# DisplayBoad.net
KiCad netlist of a schematic drawn in EAGLE
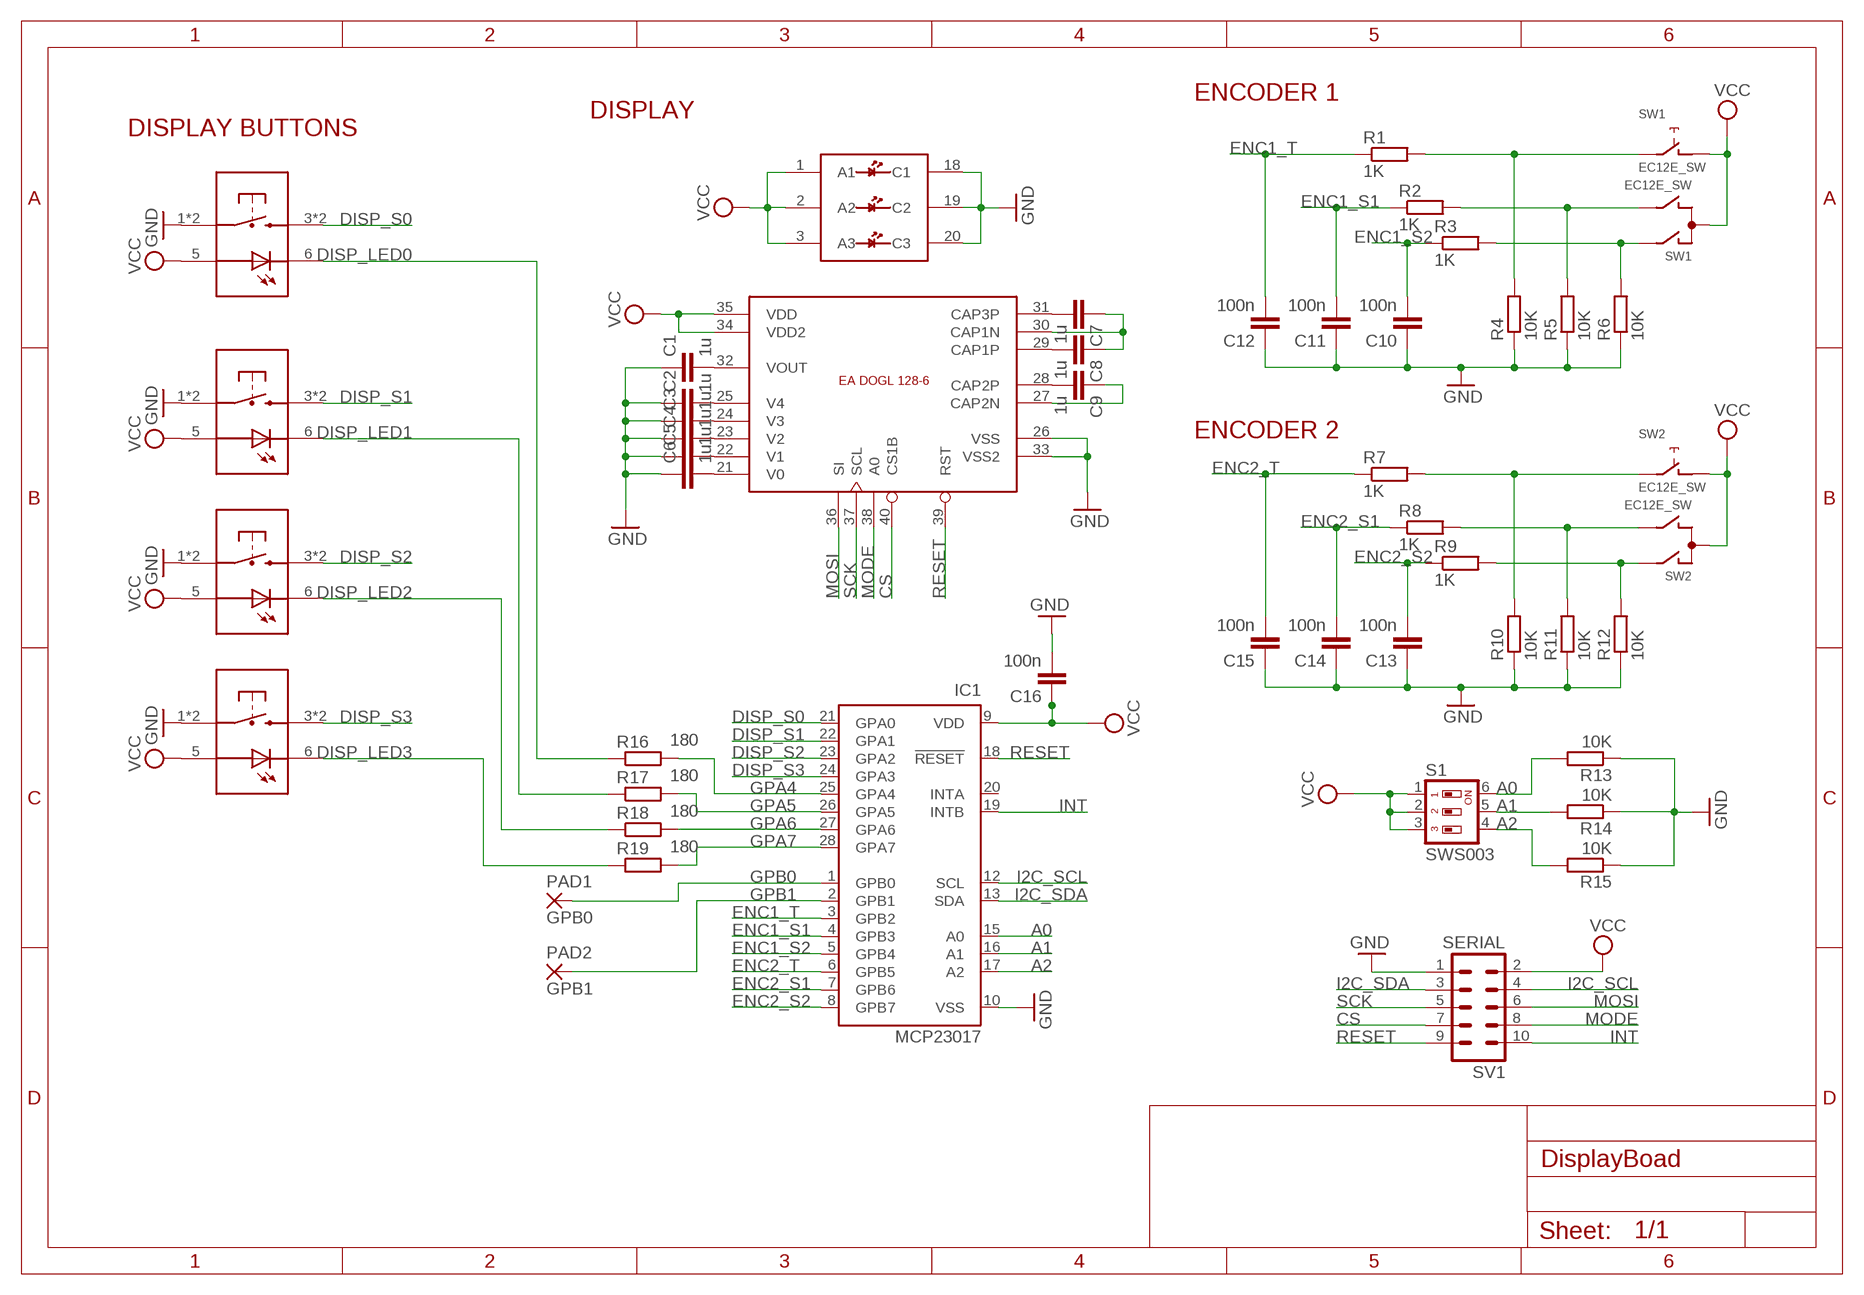
[diagram p0: schematic, sheet 1]

(export (version "E")
  (design (tool "Eeschema 10.0.6"))
  (components
    (comp (ref "C1")
      (value "1u")
      (footprint "eagle-import:C0805")
      (libsource (lib "eagle-import") (part "C-EUC0805"))
    )
    (comp (ref "C2")
      (value "1u")
      (footprint "eagle-import:C0805")
      (libsource (lib "eagle-import") (part "C-EUC0805"))
    )
    (comp (ref "C3")
      (value "1u")
      (footprint "eagle-import:C0805")
      (libsource (lib "eagle-import") (part "C-EUC0805"))
    )
    (comp (ref "C4")
      (value "1u")
      (footprint "eagle-import:C0805")
      (libsource (lib "eagle-import") (part "C-EUC0805"))
    )
    (comp (ref "C5")
      (value "1u")
      (footprint "eagle-import:C0805")
      (libsource (lib "eagle-import") (part "C-EUC0805"))
    )
    (comp (ref "C6")
      (value "1u")
      (footprint "eagle-import:C0805")
      (libsource (lib "eagle-import") (part "C-EUC0805"))
    )
    (comp (ref "C7")
      (value "1u")
      (footprint "eagle-import:C0805")
      (libsource (lib "eagle-import") (part "C-EUC0805"))
    )
    (comp (ref "C8")
      (value "1u")
      (footprint "eagle-import:C0805")
      (libsource (lib "eagle-import") (part "C-EUC0805"))
    )
    (comp (ref "C9")
      (value "1u")
      (footprint "eagle-import:C0805")
      (libsource (lib "eagle-import") (part "C-EUC0805"))
    )
    (comp (ref "C10")
      (value "100n")
      (footprint "eagle-import:C0603")
      (libsource (lib "eagle-import") (part "C-EUC0603"))
    )
    (comp (ref "C11")
      (value "100n")
      (footprint "eagle-import:C0603")
      (libsource (lib "eagle-import") (part "C-EUC0603"))
    )
    (comp (ref "C12")
      (value "100n")
      (footprint "eagle-import:C0603")
      (libsource (lib "eagle-import") (part "C-EUC0603"))
    )
    (comp (ref "C13")
      (value "100n")
      (footprint "eagle-import:C0603")
      (libsource (lib "eagle-import") (part "C-EUC0603"))
    )
    (comp (ref "C14")
      (value "100n")
      (footprint "eagle-import:C0603")
      (libsource (lib "eagle-import") (part "C-EUC0603"))
    )
    (comp (ref "C15")
      (value "100n")
      (footprint "eagle-import:C0603")
      (libsource (lib "eagle-import") (part "C-EUC0603"))
    )
    (comp (ref "C16")
      (value "100n")
      (footprint "eagle-import:C0603")
      (libsource (lib "eagle-import") (part "C-EUC0603"))
    )
    (comp (ref "IC1")
      (value "MCP23017")
      (footprint "eagle-import:SSOP28")
      (fields (field (name "MF") "MICROCHIP") (field (name "MPN") "MCP23017-E/SS"))
      (libsource (lib "eagle-import") (part "MCP23017SS"))
    )
    (comp (ref "PAD1")
      (value "GPB0")
      (footprint "eagle-import:2,15_1,0")
      (libsource (lib "eagle-import") (part "2,15/1,0"))
    )
    (comp (ref "PAD2")
      (value "GPB1")
      (footprint "eagle-import:2,15_1,0")
      (libsource (lib "eagle-import") (part "2,15/1,0"))
    )
    (comp (ref "R1")
      (value "1K")
      (footprint "eagle-import:R0603")
      (libsource (lib "eagle-import") (part "R-EU_R0603"))
    )
    (comp (ref "R2")
      (value "1K")
      (footprint "eagle-import:R0603")
      (libsource (lib "eagle-import") (part "R-EU_R0603"))
    )
    (comp (ref "R3")
      (value "1K")
      (footprint "eagle-import:R0603")
      (libsource (lib "eagle-import") (part "R-EU_R0603"))
    )
    (comp (ref "R4")
      (value "10K")
      (footprint "eagle-import:R0603")
      (libsource (lib "eagle-import") (part "R-EU_R0603"))
    )
    (comp (ref "R5")
      (value "10K")
      (footprint "eagle-import:R0603")
      (libsource (lib "eagle-import") (part "R-EU_R0603"))
    )
    (comp (ref "R6")
      (value "10K")
      (footprint "eagle-import:R0603")
      (libsource (lib "eagle-import") (part "R-EU_R0603"))
    )
    (comp (ref "R7")
      (value "1K")
      (footprint "eagle-import:R0603")
      (libsource (lib "eagle-import") (part "R-EU_R0603"))
    )
    (comp (ref "R8")
      (value "1K")
      (footprint "eagle-import:R0603")
      (libsource (lib "eagle-import") (part "R-EU_R0603"))
    )
    (comp (ref "R9")
      (value "1K")
      (footprint "eagle-import:R0603")
      (libsource (lib "eagle-import") (part "R-EU_R0603"))
    )
    (comp (ref "R10")
      (value "10K")
      (footprint "eagle-import:R0603")
      (libsource (lib "eagle-import") (part "R-EU_R0603"))
    )
    (comp (ref "R11")
      (value "10K")
      (footprint "eagle-import:R0603")
      (libsource (lib "eagle-import") (part "R-EU_R0603"))
    )
    (comp (ref "R12")
      (value "10K")
      (footprint "eagle-import:R0603")
      (libsource (lib "eagle-import") (part "R-EU_R0603"))
    )
    (comp (ref "R13")
      (value "10K")
      (footprint "eagle-import:R0603")
      (libsource (lib "eagle-import") (part "R-EU_R0603"))
    )
    (comp (ref "R14")
      (value "10K")
      (footprint "eagle-import:R0603")
      (libsource (lib "eagle-import") (part "R-EU_R0603"))
    )
    (comp (ref "R15")
      (value "10K")
      (footprint "eagle-import:R0603")
      (libsource (lib "eagle-import") (part "R-EU_R0603"))
    )
    (comp (ref "R16")
      (value "180")
      (footprint "eagle-import:R0603")
      (libsource (lib "eagle-import") (part "R-EU_R0603"))
    )
    (comp (ref "R17")
      (value "180")
      (footprint "eagle-import:R0603")
      (libsource (lib "eagle-import") (part "R-EU_R0603"))
    )
    (comp (ref "R18")
      (value "180")
      (footprint "eagle-import:R0603")
      (libsource (lib "eagle-import") (part "R-EU_R0603"))
    )
    (comp (ref "R19")
      (value "180")
      (footprint "eagle-import:R0603")
      (libsource (lib "eagle-import") (part "R-EU_R0603"))
    )
    (comp (ref "S1")
      (value "SWS003")
      (footprint "eagle-import:SMS-003")
      (libsource (lib "eagle-import") (part "SWS003"))
    )
    (comp (ref "SV1")
      (value "SERIAL")
      (footprint "eagle-import:MA05-2")
      (libsource (lib "eagle-import") (part "MA05-2"))
    )
    (comp (ref "SW1")
      (value "EC12E_SW")
      (footprint "eagle-import:ALPS_EC12E_SW")
      (fields (field (name "MPN") "EC12E2424407"))
      (libsource (lib "eagle-import") (part "EC12E_SW"))
    )
    (comp (ref "SW2")
      (value "EC12E_SW")
      (footprint "eagle-import:ALPS_EC12E_SW")
      (fields (field (name "MPN") "EC12E2424407"))
      (libsource (lib "eagle-import") (part "EC12E_SW"))
    )
    (comp (ref "U$2")
      (value "LP15")
      (footprint "eagle-import:LP15")
      (libsource (lib "eagle-import") (part "LP15"))
    )
    (comp (ref "U$3")
      (value "LP15")
      (footprint "eagle-import:LP15")
      (libsource (lib "eagle-import") (part "LP15"))
    )
    (comp (ref "U$4")
      (value "LP15")
      (footprint "eagle-import:LP15")
      (libsource (lib "eagle-import") (part "LP15"))
    )
    (comp (ref "U$5")
      (value "LP15")
      (footprint "eagle-import:LP15")
      (libsource (lib "eagle-import") (part "LP15"))
    )
    (comp (ref "U1")
      (value "EADOGL128-62")
      (footprint "eagle-import:EA_DOGL128-6")
      (libsource (lib "eagle-import") (part "EADOGL128-62"))
    )
  )
  (nets
    (net (code "1") (name "/A0") (class "Default")
      (node (ref "IC1") (pin "15") (pinfunction "A0_15") (pintype "input"))
      (node (ref "R13") (pin "2") (pinfunction "2_2") (pintype "passive"))
      (node (ref "S1") (pin "6") (pinfunction "6_6") (pintype "passive"))
    )
    (net (code "2") (name "/A1") (class "Default")
      (node (ref "IC1") (pin "16") (pinfunction "A1_16") (pintype "input"))
      (node (ref "R14") (pin "2") (pinfunction "2_2") (pintype "passive"))
      (node (ref "S1") (pin "5") (pinfunction "5_5") (pintype "passive"))
    )
    (net (code "3") (name "/A2") (class "Default")
      (node (ref "IC1") (pin "17") (pinfunction "A2_17") (pintype "input"))
      (node (ref "R15") (pin "2") (pinfunction "2_2") (pintype "passive"))
      (node (ref "S1") (pin "4") (pinfunction "4_4") (pintype "passive"))
    )
    (net (code "4") (name "/CS") (class "Default")
      (node (ref "SV1") (pin "7") (pinfunction "7_7") (pintype "passive"))
      (node (ref "U1") (pin "40") (pinfunction "CS1B_40") (pintype "input"))
    )
    (net (code "5") (name "/DISP_LED0") (class "Default")
      (node (ref "R16") (pin "1") (pinfunction "1_1") (pintype "passive"))
      (node (ref "U$2") (pin "6") (pinfunction "6_6") (pintype "bidirectional"))
    )
    (net (code "6") (name "/DISP_LED1") (class "Default")
      (node (ref "R17") (pin "1") (pinfunction "1_1") (pintype "passive"))
      (node (ref "U$3") (pin "6") (pinfunction "6_6") (pintype "bidirectional"))
    )
    (net (code "7") (name "/DISP_LED2") (class "Default")
      (node (ref "R18") (pin "1") (pinfunction "1_1") (pintype "passive"))
      (node (ref "U$4") (pin "6") (pinfunction "6_6") (pintype "bidirectional"))
    )
    (net (code "8") (name "/DISP_LED3") (class "Default")
      (node (ref "R19") (pin "1") (pinfunction "1_1") (pintype "passive"))
      (node (ref "U$5") (pin "6") (pinfunction "6_6") (pintype "bidirectional"))
    )
    (net (code "9") (name "/DISP_S0") (class "Default")
      (node (ref "IC1") (pin "21") (pinfunction "GPA0_21") (pintype "bidirectional"))
      (node (ref "U$2") (pin "3") (pinfunction "3_3") (pintype "bidirectional"))
      (node (ref "U$2") (pin "4") (pinfunction "3_4") (pintype "bidirectional"))
    )
    (net (code "10") (name "/DISP_S1") (class "Default")
      (node (ref "IC1") (pin "22") (pinfunction "GPA1_22") (pintype "bidirectional"))
      (node (ref "U$3") (pin "3") (pinfunction "3_3") (pintype "bidirectional"))
      (node (ref "U$3") (pin "4") (pinfunction "3_4") (pintype "bidirectional"))
    )
    (net (code "11") (name "/DISP_S2") (class "Default")
      (node (ref "IC1") (pin "23") (pinfunction "GPA2_23") (pintype "bidirectional"))
      (node (ref "U$4") (pin "3") (pinfunction "3_3") (pintype "bidirectional"))
      (node (ref "U$4") (pin "4") (pinfunction "3_4") (pintype "bidirectional"))
    )
    (net (code "12") (name "/DISP_S3") (class "Default")
      (node (ref "IC1") (pin "24") (pinfunction "GPA3_24") (pintype "bidirectional"))
      (node (ref "U$5") (pin "3") (pinfunction "3_3") (pintype "bidirectional"))
      (node (ref "U$5") (pin "4") (pinfunction "3_4") (pintype "bidirectional"))
    )
    (net (code "13") (name "/ENC1_S1") (class "Default")
      (node (ref "C11") (pin "2") (pinfunction "2_2") (pintype "passive"))
      (node (ref "IC1") (pin "4") (pinfunction "GPB3_4") (pintype "bidirectional"))
      (node (ref "R2") (pin "1") (pinfunction "1_1") (pintype "passive"))
    )
    (net (code "14") (name "/ENC1_S2") (class "Default")
      (node (ref "C10") (pin "2") (pinfunction "2_2") (pintype "passive"))
      (node (ref "IC1") (pin "5") (pinfunction "GPB4_5") (pintype "bidirectional"))
      (node (ref "R3") (pin "1") (pinfunction "1_1") (pintype "passive"))
    )
    (net (code "15") (name "/ENC1_T") (class "Default")
      (node (ref "C12") (pin "2") (pinfunction "2_2") (pintype "passive"))
      (node (ref "IC1") (pin "3") (pinfunction "GPB2_3") (pintype "bidirectional"))
      (node (ref "R1") (pin "1") (pinfunction "1_1") (pintype "passive"))
    )
    (net (code "16") (name "/ENC2_S1") (class "Default")
      (node (ref "C14") (pin "2") (pinfunction "2_2") (pintype "passive"))
      (node (ref "IC1") (pin "7") (pinfunction "GPB6_7") (pintype "bidirectional"))
      (node (ref "R8") (pin "1") (pinfunction "1_1") (pintype "passive"))
    )
    (net (code "17") (name "/ENC2_S2") (class "Default")
      (node (ref "C13") (pin "2") (pinfunction "2_2") (pintype "passive"))
      (node (ref "IC1") (pin "8") (pinfunction "GPB7_8") (pintype "bidirectional"))
      (node (ref "R9") (pin "1") (pinfunction "1_1") (pintype "passive"))
    )
    (net (code "18") (name "/ENC2_T") (class "Default")
      (node (ref "C15") (pin "2") (pinfunction "2_2") (pintype "passive"))
      (node (ref "IC1") (pin "6") (pinfunction "GPB5_6") (pintype "bidirectional"))
      (node (ref "R7") (pin "1") (pinfunction "1_1") (pintype "passive"))
    )
    (net (code "19") (name "/GPA4") (class "Default")
      (node (ref "IC1") (pin "25") (pinfunction "GPA4_25") (pintype "bidirectional"))
      (node (ref "R16") (pin "2") (pinfunction "2_2") (pintype "passive"))
    )
    (net (code "20") (name "/GPA5") (class "Default")
      (node (ref "IC1") (pin "26") (pinfunction "GPA5_26") (pintype "bidirectional"))
      (node (ref "R17") (pin "2") (pinfunction "2_2") (pintype "passive"))
    )
    (net (code "21") (name "/GPA6") (class "Default")
      (node (ref "IC1") (pin "27") (pinfunction "GPA6_27") (pintype "bidirectional"))
      (node (ref "R18") (pin "2") (pinfunction "2_2") (pintype "passive"))
    )
    (net (code "22") (name "/GPA7") (class "Default")
      (node (ref "IC1") (pin "28") (pinfunction "GPA7_28") (pintype "bidirectional"))
      (node (ref "R19") (pin "2") (pinfunction "2_2") (pintype "passive"))
    )
    (net (code "23") (name "/GPB0") (class "Default")
      (node (ref "IC1") (pin "1") (pinfunction "GPB0_1") (pintype "bidirectional"))
      (node (ref "PAD1") (pin "1") (pinfunction "P_1") (pintype "passive"))
    )
    (net (code "24") (name "/GPB1") (class "Default")
      (node (ref "IC1") (pin "2") (pinfunction "GPB1_2") (pintype "bidirectional"))
      (node (ref "PAD2") (pin "1") (pinfunction "P_1") (pintype "passive"))
    )
    (net (code "25") (name "/I2C_SCL") (class "Default")
      (node (ref "IC1") (pin "12") (pinfunction "SCL_12") (pintype "input"))
      (node (ref "SV1") (pin "4") (pinfunction "4_4") (pintype "passive"))
    )
    (net (code "26") (name "/I2C_SDA") (class "Default")
      (node (ref "IC1") (pin "13") (pinfunction "SDA_13") (pintype "bidirectional"))
      (node (ref "SV1") (pin "3") (pinfunction "3_3") (pintype "passive"))
    )
    (net (code "27") (name "/INT") (class "Default")
      (node (ref "IC1") (pin "19") (pinfunction "INTB_19") (pintype "output"))
      (node (ref "SV1") (pin "10") (pinfunction "10_10") (pintype "passive"))
    )
    (net (code "28") (name "/MODE") (class "Default")
      (node (ref "SV1") (pin "8") (pinfunction "8_8") (pintype "passive"))
      (node (ref "U1") (pin "38") (pinfunction "A0_38") (pintype "input"))
    )
    (net (code "29") (name "/MOSI") (class "Default")
      (node (ref "SV1") (pin "6") (pinfunction "6_6") (pintype "passive"))
      (node (ref "U1") (pin "36") (pinfunction "SI_36") (pintype "input"))
    )
    (net (code "30") (name "/RESET") (class "Default")
      (node (ref "IC1") (pin "18") (pinfunction "~{RESET}_18") (pintype "input"))
      (node (ref "SV1") (pin "9") (pinfunction "9_9") (pintype "passive"))
      (node (ref "U1") (pin "39") (pinfunction "RST_39") (pintype "bidirectional"))
    )
    (net (code "31") (name "/SCK") (class "Default")
      (node (ref "SV1") (pin "5") (pinfunction "5_5") (pintype "passive"))
      (node (ref "U1") (pin "37") (pinfunction "SCL_37") (pintype "input"))
    )
    (net (code "32") (name "GND") (class "Default")
      (node (ref "C1") (pin "1") (pinfunction "1_1") (pintype "passive"))
      (node (ref "C10") (pin "1") (pinfunction "1_1") (pintype "passive"))
      (node (ref "C11") (pin "1") (pinfunction "1_1") (pintype "passive"))
      (node (ref "C12") (pin "1") (pinfunction "1_1") (pintype "passive"))
      (node (ref "C13") (pin "1") (pinfunction "1_1") (pintype "passive"))
      (node (ref "C14") (pin "1") (pinfunction "1_1") (pintype "passive"))
      (node (ref "C15") (pin "1") (pinfunction "1_1") (pintype "passive"))
      (node (ref "C16") (pin "2") (pinfunction "2_2") (pintype "passive"))
      (node (ref "C2") (pin "1") (pinfunction "1_1") (pintype "passive"))
      (node (ref "C3") (pin "1") (pinfunction "1_1") (pintype "passive"))
      (node (ref "C4") (pin "1") (pinfunction "1_1") (pintype "passive"))
      (node (ref "C5") (pin "1") (pinfunction "1_1") (pintype "passive"))
      (node (ref "C6") (pin "1") (pinfunction "1_1") (pintype "passive"))
      (node (ref "IC1") (pin "10") (pinfunction "VSS_10") (pintype "power_in"))
      (node (ref "R10") (pin "1") (pinfunction "1_1") (pintype "passive"))
      (node (ref "R11") (pin "1") (pinfunction "1_1") (pintype "passive"))
      (node (ref "R12") (pin "1") (pinfunction "1_1") (pintype "passive"))
      (node (ref "R13") (pin "1") (pinfunction "1_1") (pintype "passive"))
      (node (ref "R14") (pin "1") (pinfunction "1_1") (pintype "passive"))
      (node (ref "R15") (pin "1") (pinfunction "1_1") (pintype "passive"))
      (node (ref "R4") (pin "1") (pinfunction "1_1") (pintype "passive"))
      (node (ref "R5") (pin "1") (pinfunction "1_1") (pintype "passive"))
      (node (ref "R6") (pin "1") (pinfunction "1_1") (pintype "passive"))
      (node (ref "SV1") (pin "1") (pinfunction "1_1") (pintype "passive"))
      (node (ref "U$2") (pin "1") (pinfunction "1_1") (pintype "bidirectional"))
      (node (ref "U$2") (pin "2") (pinfunction "1_2") (pintype "bidirectional"))
      (node (ref "U$3") (pin "1") (pinfunction "1_1") (pintype "bidirectional"))
      (node (ref "U$3") (pin "2") (pinfunction "1_2") (pintype "bidirectional"))
      (node (ref "U$4") (pin "1") (pinfunction "1_1") (pintype "bidirectional"))
      (node (ref "U$4") (pin "2") (pinfunction "1_2") (pintype "bidirectional"))
      (node (ref "U$5") (pin "1") (pinfunction "1_1") (pintype "bidirectional"))
      (node (ref "U$5") (pin "2") (pinfunction "1_2") (pintype "bidirectional"))
      (node (ref "U1") (pin "18") (pinfunction "C1_18") (pintype "bidirectional"))
      (node (ref "U1") (pin "19") (pinfunction "C2_19") (pintype "bidirectional"))
      (node (ref "U1") (pin "20") (pinfunction "C3_20") (pintype "bidirectional"))
      (node (ref "U1") (pin "26") (pinfunction "VSS_26") (pintype "power_in"))
      (node (ref "U1") (pin "33") (pinfunction "VSS2_33") (pintype "power_in"))
    )
    (net (code "33") (name "Net-(R2-Pad2)") (class "Default")
      (node (ref "R2") (pin "2") (pinfunction "2_2") (pintype "passive"))
      (node (ref "R5") (pin "2") (pinfunction "2_2") (pintype "passive"))
      (node (ref "SW1") (pin "B") (pinfunction "B_B") (pintype "passive"))
    )
    (net (code "34") (name "Net-(R3-Pad2)") (class "Default")
      (node (ref "R3") (pin "2") (pinfunction "2_2") (pintype "passive"))
      (node (ref "R6") (pin "2") (pinfunction "2_2") (pintype "passive"))
      (node (ref "SW1") (pin "A") (pinfunction "A_A") (pintype "passive"))
    )
    (net (code "35") (name "Net-(R11-Pad2)") (class "Default")
      (node (ref "R11") (pin "2") (pinfunction "2_2") (pintype "passive"))
      (node (ref "R8") (pin "2") (pinfunction "2_2") (pintype "passive"))
      (node (ref "SW2") (pin "B") (pinfunction "B_B") (pintype "passive"))
    )
    (net (code "36") (name "Net-(R12-Pad2)") (class "Default")
      (node (ref "R12") (pin "2") (pinfunction "2_2") (pintype "passive"))
      (node (ref "R9") (pin "2") (pinfunction "2_2") (pintype "passive"))
      (node (ref "SW2") (pin "A") (pinfunction "A_A") (pintype "passive"))
    )
    (net (code "37") (name "Net-(SW1B-2)") (class "Default")
      (node (ref "R1") (pin "2") (pinfunction "2_2") (pintype "passive"))
      (node (ref "R4") (pin "2") (pinfunction "2_2") (pintype "passive"))
      (node (ref "SW1") (pin "E") (pinfunction "2_E") (pintype "passive"))
    )
    (net (code "38") (name "Net-(SW2B-2)") (class "Default")
      (node (ref "R10") (pin "2") (pinfunction "2_2") (pintype "passive"))
      (node (ref "R7") (pin "2") (pinfunction "2_2") (pintype "passive"))
      (node (ref "SW2") (pin "E") (pinfunction "2_E") (pintype "passive"))
    )
    (net (code "39") (name "Net-(U1A-CAP1N)") (class "Default")
      (node (ref "C7") (pin "1") (pinfunction "1_1") (pintype "passive"))
      (node (ref "C8") (pin "1") (pinfunction "1_1") (pintype "passive"))
      (node (ref "U1") (pin "30") (pinfunction "CAP1N_30") (pintype "bidirectional"))
    )
    (net (code "40") (name "Net-(U1A-CAP1P)") (class "Default")
      (node (ref "C8") (pin "2") (pinfunction "2_2") (pintype "passive"))
      (node (ref "U1") (pin "29") (pinfunction "CAP1P_29") (pintype "bidirectional"))
    )
    (net (code "41") (name "Net-(U1A-CAP2N)") (class "Default")
      (node (ref "C9") (pin "1") (pinfunction "1_1") (pintype "passive"))
      (node (ref "U1") (pin "27") (pinfunction "CAP2N_27") (pintype "bidirectional"))
    )
    (net (code "42") (name "Net-(U1A-CAP2P)") (class "Default")
      (node (ref "C9") (pin "2") (pinfunction "2_2") (pintype "passive"))
      (node (ref "U1") (pin "28") (pinfunction "CAP2P_28") (pintype "bidirectional"))
    )
    (net (code "43") (name "Net-(U1A-CAP3P)") (class "Default")
      (node (ref "C7") (pin "2") (pinfunction "2_2") (pintype "passive"))
      (node (ref "U1") (pin "31") (pinfunction "CAP3P_31") (pintype "bidirectional"))
    )
    (net (code "44") (name "Net-(U1A-V0)") (class "Default")
      (node (ref "C6") (pin "2") (pinfunction "2_2") (pintype "passive"))
      (node (ref "U1") (pin "21") (pinfunction "V0_21") (pintype "bidirectional"))
    )
    (net (code "45") (name "Net-(U1A-V1)") (class "Default")
      (node (ref "C5") (pin "2") (pinfunction "2_2") (pintype "passive"))
      (node (ref "U1") (pin "22") (pinfunction "V1_22") (pintype "bidirectional"))
    )
    (net (code "46") (name "Net-(U1A-V2)") (class "Default")
      (node (ref "C4") (pin "2") (pinfunction "2_2") (pintype "passive"))
      (node (ref "U1") (pin "23") (pinfunction "V2_23") (pintype "bidirectional"))
    )
    (net (code "47") (name "Net-(U1A-V3)") (class "Default")
      (node (ref "C3") (pin "2") (pinfunction "2_2") (pintype "passive"))
      (node (ref "U1") (pin "24") (pinfunction "V3_24") (pintype "bidirectional"))
    )
    (net (code "48") (name "Net-(U1A-V4)") (class "Default")
      (node (ref "C2") (pin "2") (pinfunction "2_2") (pintype "passive"))
      (node (ref "U1") (pin "25") (pinfunction "V4_25") (pintype "bidirectional"))
    )
    (net (code "49") (name "Net-(U1A-VOUT)") (class "Default")
      (node (ref "C1") (pin "2") (pinfunction "2_2") (pintype "passive"))
      (node (ref "U1") (pin "32") (pinfunction "VOUT_32") (pintype "output"))
    )
    (net (code "50") (name "VCC") (class "Default")
      (node (ref "C16") (pin "1") (pinfunction "1_1") (pintype "passive"))
      (node (ref "IC1") (pin "9") (pinfunction "VDD_9") (pintype "power_in"))
      (node (ref "S1") (pin "1") (pinfunction "1_1") (pintype "passive"))
      (node (ref "S1") (pin "2") (pinfunction "2_2") (pintype "passive"))
      (node (ref "S1") (pin "3") (pinfunction "3_3") (pintype "passive"))
      (node (ref "SV1") (pin "2") (pinfunction "2_2") (pintype "passive"))
      (node (ref "SW1") (pin "C") (pinfunction "C_C") (pintype "passive"))
      (node (ref "SW1") (pin "D") (pinfunction "1_D") (pintype "passive"))
      (node (ref "SW2") (pin "C") (pinfunction "C_C") (pintype "passive"))
      (node (ref "SW2") (pin "D") (pinfunction "1_D") (pintype "passive"))
      (node (ref "U$2") (pin "5") (pinfunction "5_5") (pintype "bidirectional"))
      (node (ref "U$3") (pin "5") (pinfunction "5_5") (pintype "bidirectional"))
      (node (ref "U$4") (pin "5") (pinfunction "5_5") (pintype "bidirectional"))
      (node (ref "U$5") (pin "5") (pinfunction "5_5") (pintype "bidirectional"))
      (node (ref "U1") (pin "1") (pinfunction "A1_1") (pintype "bidirectional"))
      (node (ref "U1") (pin "2") (pinfunction "A2_2") (pintype "bidirectional"))
      (node (ref "U1") (pin "3") (pinfunction "A3_3") (pintype "bidirectional"))
      (node (ref "U1") (pin "34") (pinfunction "VDD2_34") (pintype "power_in"))
      (node (ref "U1") (pin "35") (pinfunction "VDD_35") (pintype "power_in"))
    )
    (net (code "51") (name "unconnected-(IC1-INTA-Pad20)") (class "Default")
      (node (ref "IC1") (pin "20") (pinfunction "INTA_20") (pintype "output"))
    )
  )
)
